# T10_Receiver.net
KiCad netlist of a schematic drawn in EAGLE
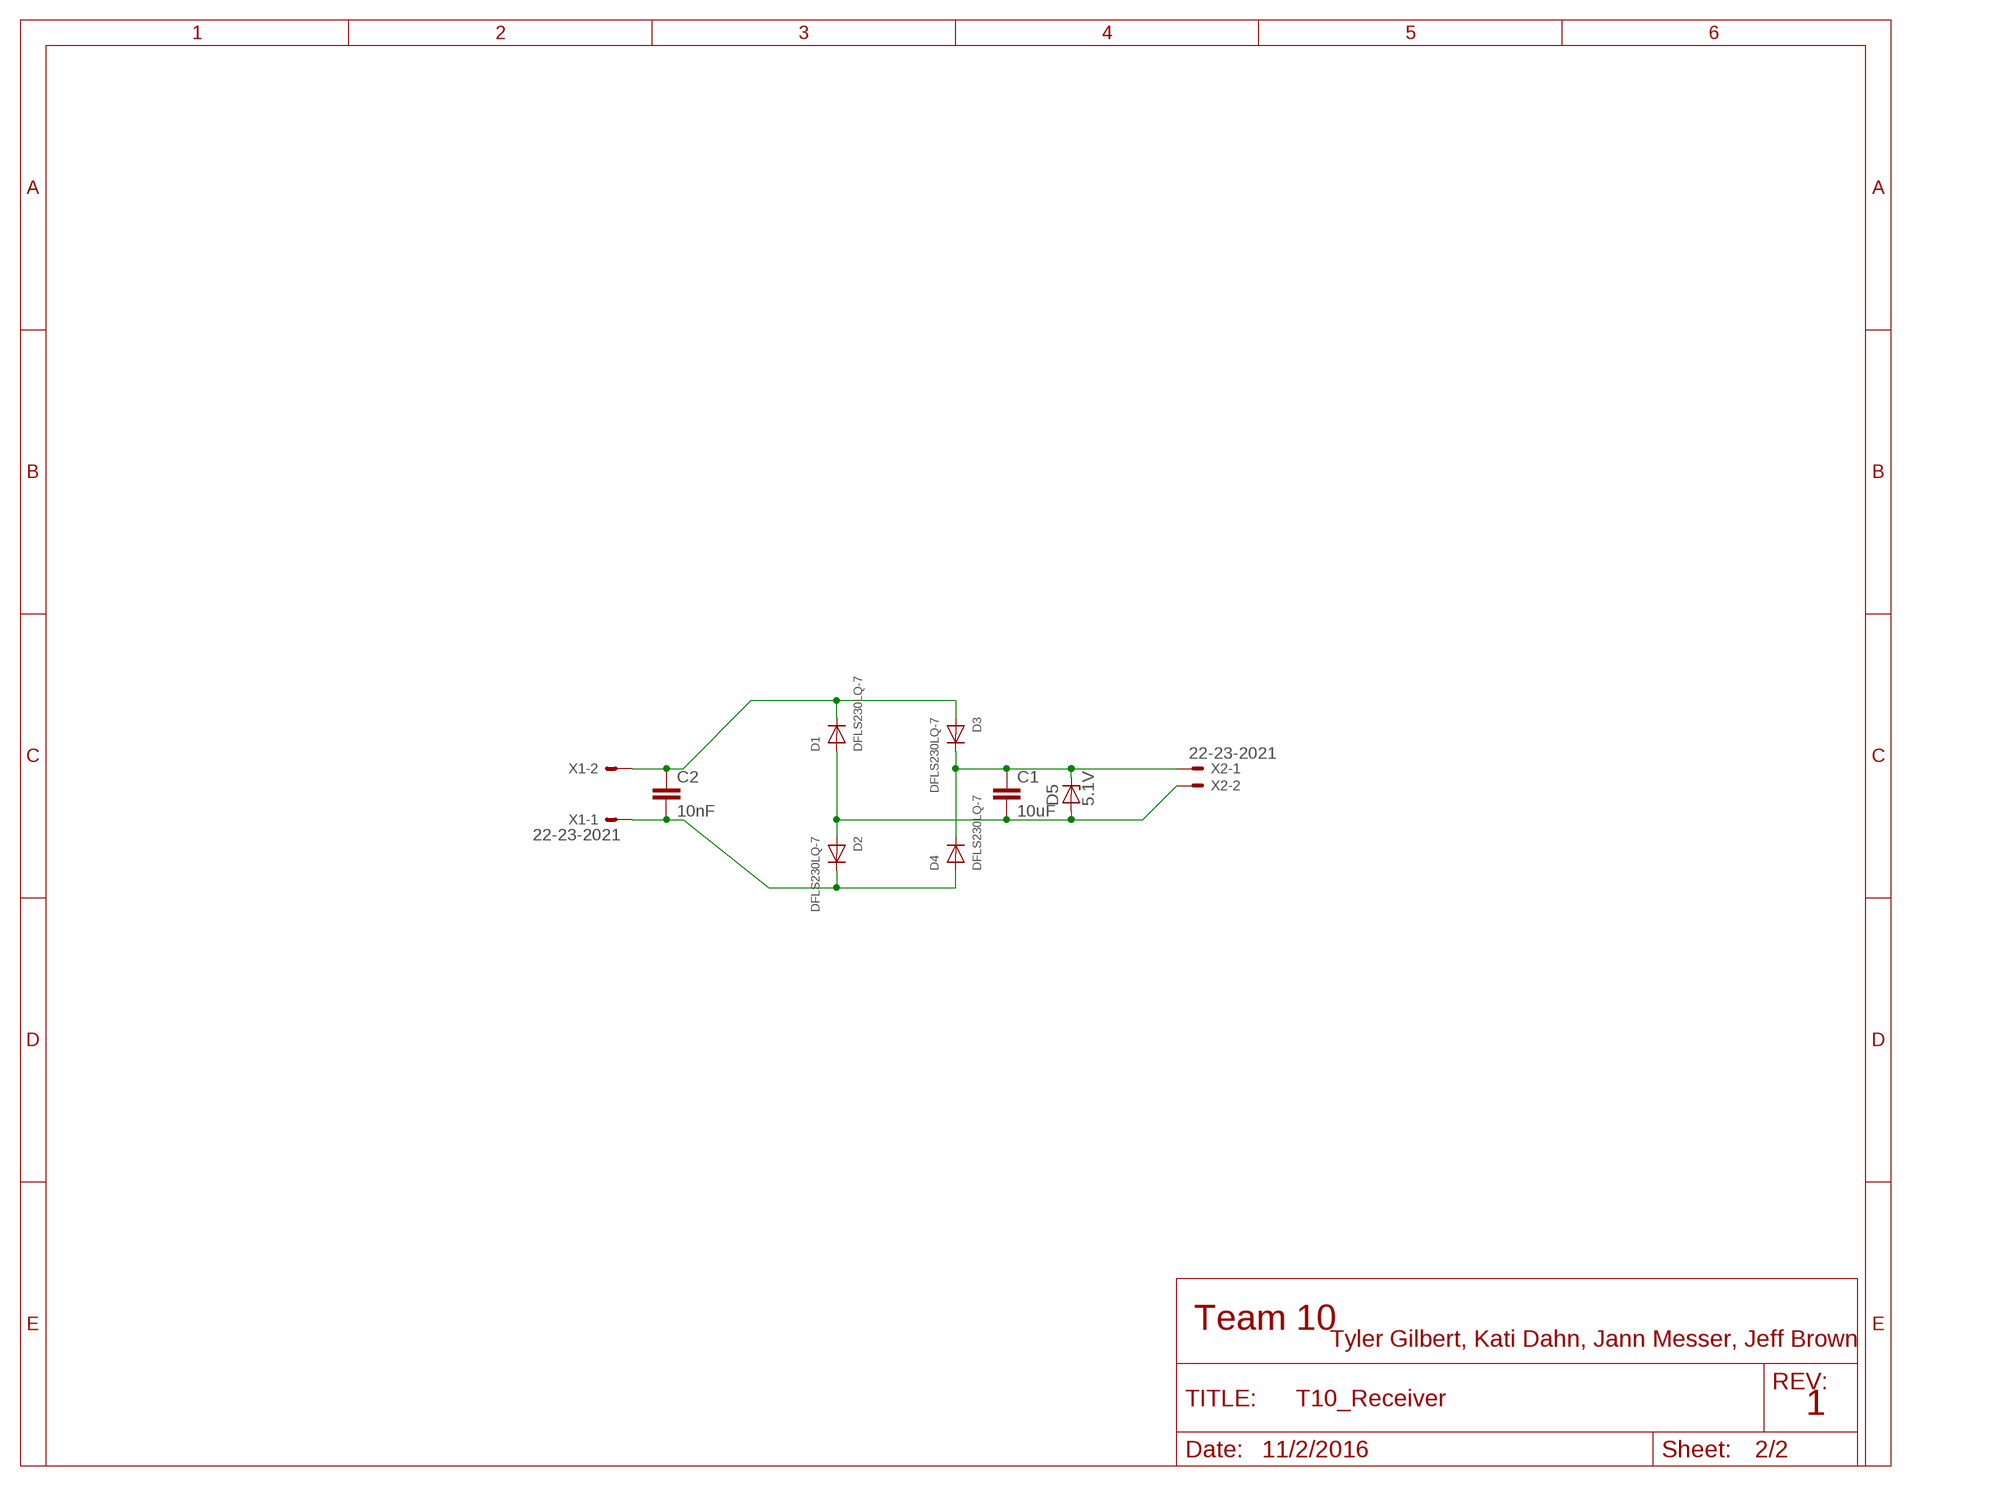
[diagram p0: schematic, sheet 1]

(export (version "E")
  (design (tool "Eeschema 10.0.6"))
  (components
    (comp (ref "C1")
      (value "10uF")
      (footprint "eagle-import:C025-030X050")
      (libsource (lib "eagle-import") (part "C-EU025-030X050"))
    )
    (comp (ref "C2")
      (value "10nF")
      (footprint "eagle-import:C025-030X050")
      (libsource (lib "eagle-import") (part "C-EU025-030X050"))
    )
    (comp (ref "D1")
      (value "DFLS230LQ-7")
      (footprint "eagle-import:SOD-523")
      (libsource (lib "eagle-import") (part "DIODESOD-523"))
    )
    (comp (ref "D2")
      (value "DFLS230LQ-7")
      (footprint "eagle-import:SOD-523")
      (libsource (lib "eagle-import") (part "DIODESOD-523"))
    )
    (comp (ref "D3")
      (value "DFLS230LQ-7")
      (footprint "eagle-import:SOD-523")
      (libsource (lib "eagle-import") (part "DIODESOD-523"))
    )
    (comp (ref "D4")
      (value "DFLS230LQ-7")
      (footprint "eagle-import:SOD-523")
      (libsource (lib "eagle-import") (part "DIODESOD-523"))
    )
    (comp (ref "D5")
      (value "5.1V")
      (footprint "eagle-import:TO236")
      (libsource (lib "eagle-import") (part "BZX84CSMD"))
    )
    (comp (ref "X1")
      (value "22-23-2021")
      (footprint "eagle-import:22-23-2021")
      (fields (field (name "MF") "MOLEX"))
      (libsource (lib "eagle-import") (part "22-23-2021"))
    )
    (comp (ref "X2")
      (value "22-23-2021")
      (footprint "eagle-import:22-23-2021")
      (fields (field (name "MF") "MOLEX"))
      (libsource (lib "eagle-import") (part "22-23-2021"))
    )
  )
  (nets
    (net (code "1") (name "Net-(D1-C)") (class "Default")
      (node (ref "C2") (pin "1") (pinfunction "1_1") (pintype "passive"))
      (node (ref "D1") (pin "K") (pinfunction "C_K") (pintype "passive"))
      (node (ref "D3") (pin "A") (pinfunction "A_A") (pintype "passive"))
      (node (ref "X1") (pin "2") (pinfunction "S_2") (pintype "passive"))
    )
    (net (code "2") (name "Net-(D2-C)") (class "Default")
      (node (ref "C2") (pin "2") (pinfunction "2_2") (pintype "passive"))
      (node (ref "D2") (pin "K") (pinfunction "C_K") (pintype "passive"))
      (node (ref "D4") (pin "A") (pinfunction "A_A") (pintype "passive"))
      (node (ref "X1") (pin "1") (pinfunction "S_1") (pintype "passive"))
    )
    (net (code "3") (name "Net-(D3-C)") (class "Default")
      (node (ref "C1") (pin "1") (pinfunction "1_1") (pintype "passive"))
      (node (ref "D3") (pin "K") (pinfunction "C_K") (pintype "passive"))
      (node (ref "D4") (pin "K") (pinfunction "C_K") (pintype "passive"))
      (node (ref "D5") (pin "C") (pinfunction "C_C") (pintype "passive"))
      (node (ref "X2") (pin "1") (pinfunction "S_1") (pintype "passive"))
    )
    (net (code "4") (name "Net-(X2B-S)") (class "Default")
      (node (ref "C1") (pin "2") (pinfunction "2_2") (pintype "passive"))
      (node (ref "D1") (pin "A") (pinfunction "A_A") (pintype "passive"))
      (node (ref "D2") (pin "A") (pinfunction "A_A") (pintype "passive"))
      (node (ref "D5") (pin "A") (pinfunction "A_A") (pintype "passive"))
      (node (ref "X2") (pin "2") (pinfunction "S_2") (pintype "passive"))
    )
  )
)
